# dedo_prog.net
KiCad netlist of a schematic drawn in EAGLE
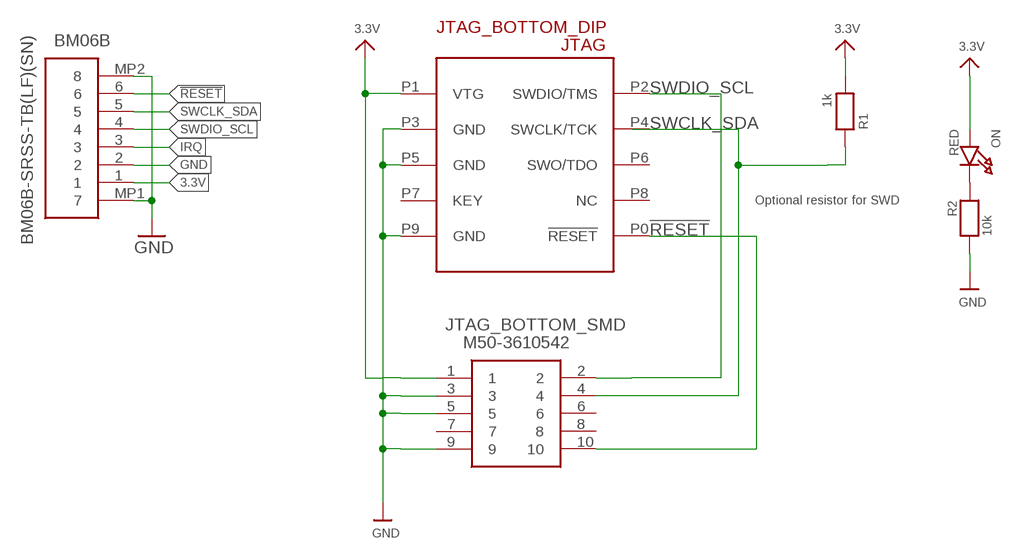
[diagram p0: schematic, sheet 1]

(export (version "E")
  (design (tool "Eeschema 10.0.6"))
  (components
    (comp (ref "BM06B")
      (value "BM06B-SRSS-TB(LF)(SN)")
      (footprint "eagle-import:BM06BSRSSTBLFSN")
      (fields (field (name "RS_PART_NUMBER") "5468782"))
      (libsource (lib "eagle-import") (part "BM06B-SRSS-TB(LF)(SN)"))
    )
    (comp (ref "JTAG_BOTTOM_DIP")
      (value "JTAGICE3-CONNECTOR50MIL-THT")
      (footprint "eagle-import:JTAGICE3-50MIL")
      (libsource (lib "eagle-import") (part "JTAGICE3-CONNECTOR50MIL-THT"))
    )
    (comp (ref "JTAG_BOTTOM_SMD")
      (value "M50-3610542")
      (footprint "eagle-import:M503610542")
      (fields (field (name "MOUSER_PART_NUMBER") "855-M50-3610542"))
      (libsource (lib "eagle-import") (part "M50-3610542"))
    )
    (comp (ref "ON")
      (value "RED")
      (footprint "eagle-import:CHIPLED_0603")
      (libsource (lib "eagle-import") (part "LED0603"))
    )
    (comp (ref "R1")
      (value "1k")
      (footprint "eagle-import:_0402@1")
      (libsource (lib "eagle-import") (part "RESISTOR_0402"))
    )
    (comp (ref "R2")
      (value "10k")
      (footprint "eagle-import:_0402@1")
      (libsource (lib "eagle-import") (part "RESISTOR_0402"))
    )
  )
  (nets
    (net (code "1") (name "/~{RESET}") (class "Default")
      (node (ref "BM06B") (pin "6") (pinfunction "6_6") (pintype "bidirectional"))
      (node (ref "JTAG_BOTTOM_DIP") (pin "P0") (pinfunction "~{RESET}_P0") (pintype "bidirectional"))
      (node (ref "JTAG_BOTTOM_SMD") (pin "10") (pinfunction "10_10") (pintype "bidirectional"))
    )
    (net (code "2") (name "3.3V") (class "Default")
      (node (ref "BM06B") (pin "1") (pinfunction "1_1") (pintype "bidirectional"))
      (node (ref "JTAG_BOTTOM_DIP") (pin "P1") (pinfunction "VTG_P1") (pintype "bidirectional"))
      (node (ref "JTAG_BOTTOM_SMD") (pin "1") (pinfunction "1_1") (pintype "bidirectional"))
      (node (ref "ON") (pin "A") (pinfunction "A_A") (pintype "passive"))
      (node (ref "R1") (pin "2") (pinfunction "2_2") (pintype "passive"))
    )
    (net (code "3") (name "GND") (class "Default")
      (node (ref "BM06B") (pin "2") (pinfunction "2_2") (pintype "bidirectional"))
      (node (ref "BM06B") (pin "MP1") (pinfunction "7_MP1") (pintype "bidirectional"))
      (node (ref "BM06B") (pin "MP2") (pinfunction "8_MP2") (pintype "bidirectional"))
      (node (ref "JTAG_BOTTOM_DIP") (pin "P3") (pinfunction "GND_P3") (pintype "bidirectional"))
      (node (ref "JTAG_BOTTOM_DIP") (pin "P5") (pinfunction "GND_P5") (pintype "bidirectional"))
      (node (ref "JTAG_BOTTOM_DIP") (pin "P9") (pinfunction "GND_P9") (pintype "bidirectional"))
      (node (ref "JTAG_BOTTOM_SMD") (pin "3") (pinfunction "3_3") (pintype "bidirectional"))
      (node (ref "JTAG_BOTTOM_SMD") (pin "5") (pinfunction "5_5") (pintype "bidirectional"))
      (node (ref "JTAG_BOTTOM_SMD") (pin "9") (pinfunction "9_9") (pintype "bidirectional"))
      (node (ref "R2") (pin "1") (pinfunction "1_1") (pintype "passive"))
    )
    (net (code "4") (name "IRQ") (class "Default")
      (node (ref "BM06B") (pin "3") (pinfunction "3_3") (pintype "bidirectional"))
    )
    (net (code "5") (name "Net-(ON-PadC)") (class "Default")
      (node (ref "ON") (pin "C") (pinfunction "C_C") (pintype "passive"))
      (node (ref "R2") (pin "2") (pinfunction "2_2") (pintype "passive"))
    )
    (net (code "6") (name "SWCLK_SDA") (class "Default")
      (node (ref "BM06B") (pin "5") (pinfunction "5_5") (pintype "bidirectional"))
      (node (ref "JTAG_BOTTOM_DIP") (pin "P4") (pinfunction "SWCLK/TCK_P4") (pintype "bidirectional"))
      (node (ref "JTAG_BOTTOM_SMD") (pin "4") (pinfunction "4_4") (pintype "bidirectional"))
      (node (ref "R1") (pin "1") (pinfunction "1_1") (pintype "passive"))
    )
    (net (code "7") (name "SWDIO_SCL") (class "Default")
      (node (ref "BM06B") (pin "4") (pinfunction "4_4") (pintype "bidirectional"))
      (node (ref "JTAG_BOTTOM_DIP") (pin "P2") (pinfunction "SWDIO/TMS_P2") (pintype "bidirectional"))
      (node (ref "JTAG_BOTTOM_SMD") (pin "2") (pinfunction "2_2") (pintype "bidirectional"))
    )
    (net (code "8") (name "unconnected-(JTAG_BOTTOM_DIP-KEY-PadP7)") (class "Default")
      (node (ref "JTAG_BOTTOM_DIP") (pin "P7") (pinfunction "KEY_P7") (pintype "bidirectional"))
    )
    (net (code "9") (name "unconnected-(JTAG_BOTTOM_DIP-NC-PadP8)") (class "Default")
      (node (ref "JTAG_BOTTOM_DIP") (pin "P8") (pinfunction "NC_P8") (pintype "bidirectional"))
    )
    (net (code "10") (name "unconnected-(JTAG_BOTTOM_DIP-SWO{slash}TDO-PadP6)") (class "Default")
      (node (ref "JTAG_BOTTOM_DIP") (pin "P6") (pinfunction "SWO/TDO_P6") (pintype "bidirectional"))
    )
    (net (code "11") (name "unconnected-(JTAG_BOTTOM_SMD-Pad6)") (class "Default")
      (node (ref "JTAG_BOTTOM_SMD") (pin "6") (pinfunction "6_6") (pintype "bidirectional"))
    )
    (net (code "12") (name "unconnected-(JTAG_BOTTOM_SMD-Pad7)") (class "Default")
      (node (ref "JTAG_BOTTOM_SMD") (pin "7") (pinfunction "7_7") (pintype "bidirectional"))
    )
    (net (code "13") (name "unconnected-(JTAG_BOTTOM_SMD-Pad8)") (class "Default")
      (node (ref "JTAG_BOTTOM_SMD") (pin "8") (pinfunction "8_8") (pintype "bidirectional"))
    )
  )
)
